# sensor-small.net
KiCad netlist of a schematic drawn in EAGLE
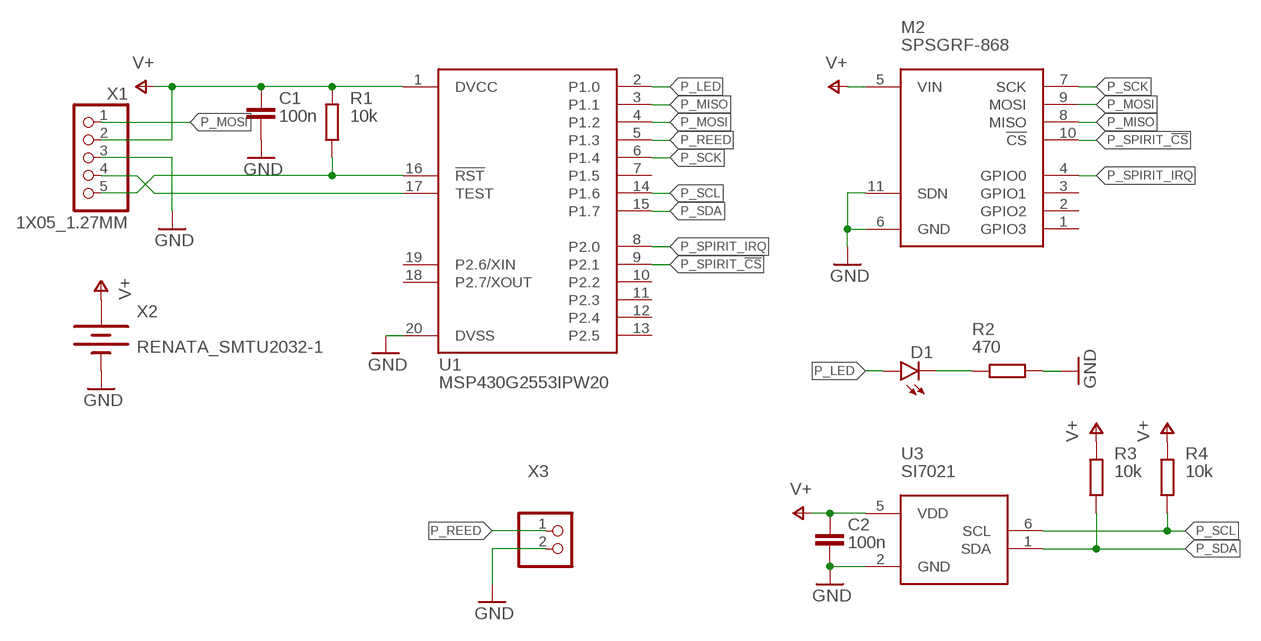
[diagram p0: schematic, sheet 1]

(export (version "E")
  (design (tool "Eeschema 10.0.6"))
  (components
    (comp (ref "C1")
      (value "100n")
      (footprint "eagle-import:C0603")
      (libsource (lib "eagle-import") (part "C0603"))
    )
    (comp (ref "C2")
      (value "100n")
      (footprint "eagle-import:C0603")
      (libsource (lib "eagle-import") (part "C0603"))
    )
    (comp (ref "D1")
      (value "LEDCHIPLED_0805")
      (footprint "eagle-import:CHIPLED_0805")
      (libsource (lib "eagle-import") (part "LEDCHIPLED_0805"))
    )
    (comp (ref "M2")
      (value "SPSGRF-868")
      (footprint "eagle-import:SPSGRF-868")
      (libsource (lib "eagle-import") (part "SPSGRF-868"))
    )
    (comp (ref "R1")
      (value "10k")
      (footprint "eagle-import:R0603")
      (libsource (lib "eagle-import") (part "R0603"))
    )
    (comp (ref "R2")
      (value "470")
      (footprint "eagle-import:R0603")
      (libsource (lib "eagle-import") (part "R0603"))
    )
    (comp (ref "R3")
      (value "10k")
      (footprint "eagle-import:R0603")
      (libsource (lib "eagle-import") (part "R0603"))
    )
    (comp (ref "R4")
      (value "10k")
      (footprint "eagle-import:R0603")
      (libsource (lib "eagle-import") (part "R0603"))
    )
    (comp (ref "U1")
      (value "MSP430G2553IPW20")
      (footprint "eagle-import:PW20")
      (libsource (lib "eagle-import") (part "MSP430G2553IPW20"))
    )
    (comp (ref "U3")
      (value "SI7021")
      (footprint "eagle-import:DFN6-3X3")
      (libsource (lib "eagle-import") (part "SI7021"))
    )
    (comp (ref "X1")
      (value "1X05_1.27MM")
      (footprint "eagle-import:1X05_1.27MM")
      (libsource (lib "eagle-import") (part "1X05_1.27MM"))
    )
    (comp (ref "X2")
      (value "RENATA_SMTU2032-1")
      (footprint "eagle-import:RENATA_SMTU2032-1")
      (libsource (lib "eagle-import") (part "RENATA_SMTU2032-1"))
    )
    (comp (ref "X3")
      (value "PINHD_2_RND")
      (footprint "eagle-import:1X02")
      (libsource (lib "eagle-import") (part "PINHD_2_RND"))
    )
  )
  (nets
    (net (code "1") (name "/P_SPIRIT_~{CS}") (class "Default")
      (node (ref "M2") (pin "10") (pinfunction "~{CS}_10") (pintype "input"))
      (node (ref "U1") (pin "9") (pinfunction "P2.1_9") (pintype "bidirectional"))
    )
    (net (code "2") (name "GND") (class "Default")
      (node (ref "C1") (pin "2") (pinfunction "2_2") (pintype "passive"))
      (node (ref "C2") (pin "2") (pinfunction "2_2") (pintype "passive"))
      (node (ref "M2") (pin "11") (pinfunction "SDN_11") (pintype "input"))
      (node (ref "M2") (pin "6") (pinfunction "GND_6") (pintype "power_in"))
      (node (ref "R2") (pin "2") (pinfunction "2_2") (pintype "passive"))
      (node (ref "U1") (pin "20") (pinfunction "DVSS_20") (pintype "bidirectional"))
      (node (ref "U3") (pin "2") (pinfunction "GND_2") (pintype "power_in"))
      (node (ref "X1") (pin "3") (pinfunction "3_3") (pintype "passive"))
      (node (ref "X2") (pin "2") (pinfunction "-_2") (pintype "power_in"))
      (node (ref "X3") (pin "2") (pinfunction "2_2") (pintype "passive"))
    )
    (net (code "3") (name "Net-(D1-PadC)") (class "Default")
      (node (ref "D1") (pin "C") (pinfunction "C_C") (pintype "passive"))
      (node (ref "R2") (pin "1") (pinfunction "1_1") (pintype "passive"))
    )
    (net (code "4") (name "Net-(U1-TEST)") (class "Default")
      (node (ref "U1") (pin "17") (pinfunction "TEST_17") (pintype "bidirectional"))
      (node (ref "X1") (pin "4") (pinfunction "4_4") (pintype "passive"))
    )
    (net (code "5") (name "Net-(U1-~{RST})") (class "Default")
      (node (ref "R1") (pin "1") (pinfunction "1_1") (pintype "passive"))
      (node (ref "U1") (pin "16") (pinfunction "~{RST}_16") (pintype "bidirectional"))
      (node (ref "X1") (pin "5") (pinfunction "5_5") (pintype "passive"))
    )
    (net (code "6") (name "P_LED") (class "Default")
      (node (ref "D1") (pin "A") (pinfunction "A_A") (pintype "passive"))
      (node (ref "U1") (pin "2") (pinfunction "P1.0_2") (pintype "bidirectional"))
    )
    (net (code "7") (name "P_MISO") (class "Default")
      (node (ref "M2") (pin "8") (pinfunction "MISO_8") (pintype "bidirectional"))
      (node (ref "U1") (pin "3") (pinfunction "P1.1_3") (pintype "bidirectional"))
    )
    (net (code "8") (name "P_MOSI") (class "Default")
      (node (ref "M2") (pin "9") (pinfunction "MOSI_9") (pintype "input"))
      (node (ref "U1") (pin "4") (pinfunction "P1.2_4") (pintype "bidirectional"))
      (node (ref "X1") (pin "1") (pinfunction "1_1") (pintype "passive"))
    )
    (net (code "9") (name "P_REED") (class "Default")
      (node (ref "U1") (pin "5") (pinfunction "P1.3_5") (pintype "bidirectional"))
      (node (ref "X3") (pin "1") (pinfunction "1_1") (pintype "passive"))
    )
    (net (code "10") (name "P_SCK") (class "Default")
      (node (ref "M2") (pin "7") (pinfunction "SCK_7") (pintype "input"))
      (node (ref "U1") (pin "6") (pinfunction "P1.4_6") (pintype "bidirectional"))
    )
    (net (code "11") (name "P_SCL") (class "Default")
      (node (ref "R4") (pin "1") (pinfunction "1_1") (pintype "passive"))
      (node (ref "U1") (pin "14") (pinfunction "P1.6_14") (pintype "bidirectional"))
      (node (ref "U3") (pin "6") (pinfunction "SCL_6") (pintype "input"))
    )
    (net (code "12") (name "P_SDA") (class "Default")
      (node (ref "R3") (pin "1") (pinfunction "1_1") (pintype "passive"))
      (node (ref "U1") (pin "15") (pinfunction "P1.7_15") (pintype "bidirectional"))
      (node (ref "U3") (pin "1") (pinfunction "SDA_1") (pintype "input"))
    )
    (net (code "13") (name "P_SPIRIT_IRQ") (class "Default")
      (node (ref "M2") (pin "4") (pinfunction "GPIO0_4") (pintype "bidirectional"))
      (node (ref "U1") (pin "8") (pinfunction "P2.0_8") (pintype "bidirectional"))
    )
    (net (code "14") (name "V+") (class "Default")
      (node (ref "C1") (pin "1") (pinfunction "1_1") (pintype "passive"))
      (node (ref "C2") (pin "1") (pinfunction "1_1") (pintype "passive"))
      (node (ref "M2") (pin "5") (pinfunction "VIN_5") (pintype "power_in"))
      (node (ref "R1") (pin "2") (pinfunction "2_2") (pintype "passive"))
      (node (ref "R3") (pin "2") (pinfunction "2_2") (pintype "passive"))
      (node (ref "R4") (pin "2") (pinfunction "2_2") (pintype "passive"))
      (node (ref "U1") (pin "1") (pinfunction "DVCC_1") (pintype "bidirectional"))
      (node (ref "U3") (pin "5") (pinfunction "VDD_5") (pintype "input"))
      (node (ref "X1") (pin "2") (pinfunction "2_2") (pintype "passive"))
      (node (ref "X2") (pin "1") (pinfunction "+_1") (pintype "power_in"))
    )
    (net (code "15") (name "unconnected-(M2-GPIO1-Pad3)") (class "Default")
      (node (ref "M2") (pin "3") (pinfunction "GPIO1_3") (pintype "bidirectional"))
    )
    (net (code "16") (name "unconnected-(M2-GPIO2-Pad2)") (class "Default")
      (node (ref "M2") (pin "2") (pinfunction "GPIO2_2") (pintype "bidirectional"))
    )
    (net (code "17") (name "unconnected-(M2-GPIO3-Pad1)") (class "Default")
      (node (ref "M2") (pin "1") (pinfunction "GPIO3_1") (pintype "bidirectional"))
    )
    (net (code "18") (name "unconnected-(U1-P1.5-Pad7)") (class "Default")
      (node (ref "U1") (pin "7") (pinfunction "P1.5_7") (pintype "bidirectional"))
    )
    (net (code "19") (name "unconnected-(U1-P2.2-Pad10)") (class "Default")
      (node (ref "U1") (pin "10") (pinfunction "P2.2_10") (pintype "bidirectional"))
    )
    (net (code "20") (name "unconnected-(U1-P2.3-Pad11)") (class "Default")
      (node (ref "U1") (pin "11") (pinfunction "P2.3_11") (pintype "bidirectional"))
    )
    (net (code "21") (name "unconnected-(U1-P2.4-Pad12)") (class "Default")
      (node (ref "U1") (pin "12") (pinfunction "P2.4_12") (pintype "bidirectional"))
    )
    (net (code "22") (name "unconnected-(U1-P2.5-Pad13)") (class "Default")
      (node (ref "U1") (pin "13") (pinfunction "P2.5_13") (pintype "bidirectional"))
    )
    (net (code "23") (name "unconnected-(U1-P2.6{slash}XIN-Pad19)") (class "Default")
      (node (ref "U1") (pin "19") (pinfunction "P2.6/XIN_19") (pintype "bidirectional"))
    )
    (net (code "24") (name "unconnected-(U1-P2.7{slash}XOUT-Pad18)") (class "Default")
      (node (ref "U1") (pin "18") (pinfunction "P2.7/XOUT_18") (pintype "bidirectional"))
    )
  )
)
